# Camera.net
KiCad netlist of a schematic drawn in Altium Designer
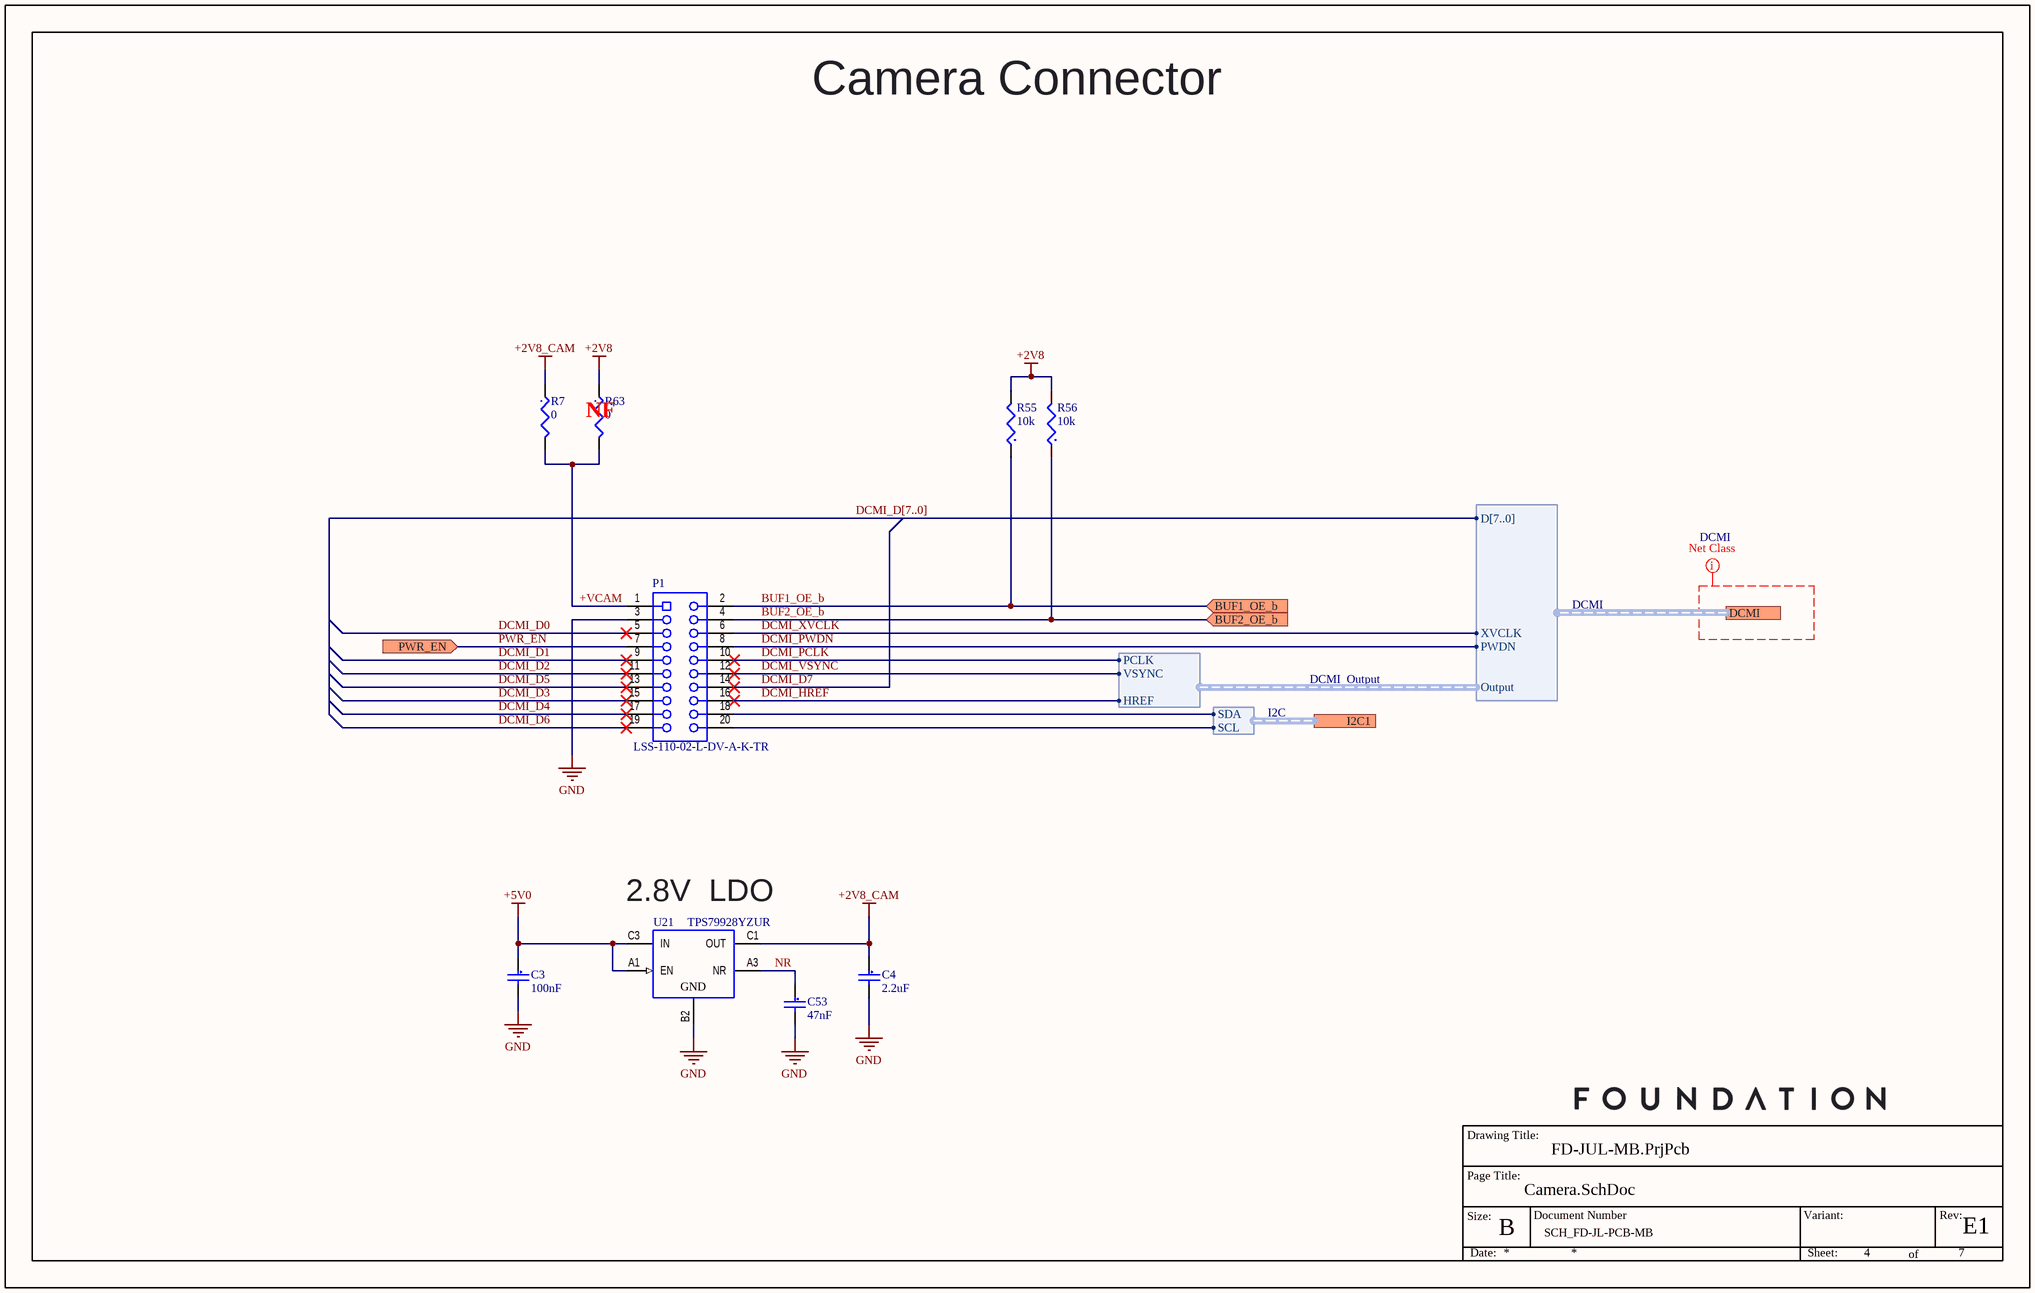
[diagram p0: Camera.SchDoc]

(export (version "E")
  (design (tool "Eeschema 10.0.6"))
  (components
    (comp (ref "C3")
      (value "CAP CER 0.1uF 16V 10% X7R 0402")
      (footprint "CAPC0402(1005)55_L")
      (description "0.1µF ±10% 16V Ceramic Capacitor X7R 0402 (1005 Metric)")
      (fields
        (field (name "CAPACITANCE") "100nF")
        (field (name "TOLERANCE") "10%")
        (field (name "VOLTAGE") "16V")
      )
      (libsource (lib "Altium Concord Pro on A365") (part "CAP-NP-2"))
    )
    (comp (ref "C4")
      (value "CAP CER 2.2uF 6.3V 10% X5R 0402")
      (footprint "CAPC0402(1005)55_L")
      (description "2.2µF ±10% 6.3V Ceramic Capacitor X5R 0402 (1005 Metric)")
      (fields (field (name "CAPACITANCE") "2.2uF") (field (name "TOLERANCE") "10%"))
      (libsource (lib "Altium Concord Pro on A365") (part "CAP-NP-2"))
    )
    (comp (ref "C53")
      (value "CAP CER 0.047uF 10V 10% X7R 0402")
      (footprint "CAPC0402(1005)55_L")
      (description "0.047µF ±10% 10V Ceramic Capacitor X7R 0402 (1005 Metric)")
      (fields (field (name "CAPACITANCE") "47nF"))
      (libsource (lib "Altium Concord Pro on A365") (part "CAP-NP-2"))
    )
    (comp (ref "P1")
      (value "LSS-110-02-L-DV-A-K-TR")
      (footprint "SMTC - LSS-110-02-L-DV-A_V")
      (description "20 Position Connector Self Mating, Non-Gendered Surface Mount Gold")
      (libsource (lib "Altium Concord Pro on A365") (part "CN-2P-F-R20"))
    )
    (comp (ref "R7")
      (value "RES 0 OHM JUMPER 1/16W 0402")
      (footprint "RESC0402(1005)_L")
      (description "0 Ohms Jumper 0.063W, 1/16W Chip Resistor 0402 (1005 Metric)")
      (fields (field (name "RESISTANCE") "0") (field (name "TOLERANCE") "5%"))
      (libsource (lib "Altium Concord Pro on A365") (part "RES-2"))
    )
    (comp (ref "R55")
      (value "RES 10K 1/16W 1% 0402")
      (footprint "RESC0402(1005)_L")
      (description "10 kOhms ±1% 0.063W, 1/16W Chip Resistor 0402 (1005 Metric)")
      (fields (field (name "RESISTANCE") "10k") (field (name "TOLERANCE") "1%"))
      (libsource (lib "Altium Concord Pro on A365") (part "RES-2"))
    )
    (comp (ref "R56")
      (value "RES 10K 1/16W 1% 0402")
      (footprint "RESC0402(1005)_L")
      (description "10 kOhms ±1% 0.063W, 1/16W Chip Resistor 0402 (1005 Metric)")
      (fields (field (name "RESISTANCE") "10k") (field (name "TOLERANCE") "1%"))
      (libsource (lib "Altium Concord Pro on A365") (part "RES-2"))
    )
    (comp (ref "R63")
      (value "RES 0 OHM JUMPER 1/16W 0402")
      (footprint "RESC0402(1005)_L")
      (description "0 Ohms Jumper 0.063W, 1/16W Chip Resistor 0402 (1005 Metric)")
      (fields (field (name "RESISTANCE") "0") (field (name "TOLERANCE") "5%"))
      (libsource (lib "Altium Concord Pro on A365") (part "RES-2"))
    )
    (comp (ref "U21")
      (value "TPS79928YZUR")
      (footprint "TI - DSBGA-YZU-5_V")
      (description "Linear Voltage Regulator IC  1 Output  200mA 5-DSBGA (1x1.37)")
      (libsource (lib "Altium Concord Pro on A365") (part "TPS79928YZU"))
    )
  )
  (nets
    (net (code "4") (name "+2V8") (class "Default")
      (node (ref "R55") (pin "2") (pinfunction "2_2") (pintype "passive"))
      (node (ref "R56") (pin "2") (pinfunction "2_2") (pintype "passive"))
      (node (ref "R63") (pin "1") (pinfunction "1_1") (pintype "passive"))
    )
    (net (code "5") (name "+2V8_CAM") (class "Default")
      (node (ref "C4") (pin "1") (pinfunction "1_1") (pintype "passive"))
      (node (ref "R7") (pin "1") (pinfunction "1_1") (pintype "passive"))
      (node (ref "U21") (pin "C1") (pinfunction "OUT_C1") (pintype "power_in"))
    )
    (net (code "6") (name "+5V0") (class "Default")
      (node (ref "C3") (pin "1") (pinfunction "1_1") (pintype "passive"))
      (node (ref "U21") (pin "A1") (pinfunction "EN_A1") (pintype "input"))
      (node (ref "U21") (pin "C3") (pinfunction "IN_C3") (pintype "power_in"))
    )
    (net (code "7") (name "/+VCAM") (class "Default")
      (node (ref "P1") (pin "1") (pinfunction "1_1") (pintype "passive"))
      (node (ref "R63") (pin "2") (pinfunction "2_2") (pintype "passive"))
      (node (ref "R7") (pin "2") (pinfunction "2_2") (pintype "passive"))
    )
    (net (code "8") (name "/BUF1_OE_b") (class "Default")
      (node (ref "P1") (pin "2") (pinfunction "2_2") (pintype "passive"))
      (node (ref "R55") (pin "1") (pinfunction "1_1") (pintype "passive"))
    )
    (net (code "9") (name "/BUF2_OE_b") (class "Default")
      (node (ref "P1") (pin "4") (pinfunction "4_4") (pintype "passive"))
      (node (ref "R56") (pin "1") (pinfunction "1_1") (pintype "passive"))
    )
    (net (code "10") (name "/DCMI_D0") (class "Default")
      (node (ref "P1") (pin "5") (pinfunction "5_5") (pintype "passive+no_connect"))
    )
    (net (code "11") (name "/DCMI_D1") (class "Default")
      (node (ref "P1") (pin "9") (pinfunction "9_9") (pintype "passive+no_connect"))
    )
    (net (code "12") (name "/DCMI_D2") (class "Default")
      (node (ref "P1") (pin "11") (pinfunction "11_11") (pintype "passive+no_connect"))
    )
    (net (code "13") (name "/DCMI_D3") (class "Default")
      (node (ref "P1") (pin "15") (pinfunction "15_15") (pintype "passive+no_connect"))
    )
    (net (code "14") (name "/DCMI_D4") (class "Default")
      (node (ref "P1") (pin "17") (pinfunction "17_17") (pintype "passive+no_connect"))
    )
    (net (code "15") (name "/DCMI_D5") (class "Default")
      (node (ref "P1") (pin "13") (pinfunction "13_13") (pintype "passive+no_connect"))
    )
    (net (code "16") (name "/DCMI_D6") (class "Default")
      (node (ref "P1") (pin "19") (pinfunction "19_19") (pintype "passive+no_connect"))
    )
    (net (code "17") (name "/DCMI_D7") (class "Default")
      (node (ref "P1") (pin "14") (pinfunction "14_14") (pintype "passive+no_connect"))
    )
    (net (code "19") (name "/DCMI_HREF") (class "Default")
      (node (ref "P1") (pin "16") (pinfunction "16_16") (pintype "passive+no_connect"))
    )
    (net (code "20") (name "/DCMI_PCLK") (class "Default")
      (node (ref "P1") (pin "10") (pinfunction "10_10") (pintype "passive+no_connect"))
    )
    (net (code "21") (name "/DCMI_PWDN") (class "Default")
      (node (ref "P1") (pin "8") (pinfunction "8_8") (pintype "passive"))
    )
    (net (code "22") (name "/DCMI_VSYNC") (class "Default")
      (node (ref "P1") (pin "12") (pinfunction "12_12") (pintype "passive+no_connect"))
    )
    (net (code "23") (name "/DCMI_XVCLK") (class "Default")
      (node (ref "P1") (pin "6") (pinfunction "6_6") (pintype "passive"))
    )
    (net (code "24") (name "/NR") (class "Default")
      (node (ref "C53") (pin "1") (pinfunction "1_1") (pintype "passive"))
      (node (ref "U21") (pin "A3") (pinfunction "NR_A3") (pintype "passive"))
    )
    (net (code "25") (name "/PWR_EN") (class "Default")
      (node (ref "P1") (pin "7") (pinfunction "7_7") (pintype "passive"))
    )
    (net (code "26") (name "/SCL") (class "Default")
      (node (ref "P1") (pin "20") (pinfunction "20_20") (pintype "passive"))
    )
    (net (code "27") (name "/SDA") (class "Default")
      (node (ref "P1") (pin "18") (pinfunction "18_18") (pintype "passive"))
    )
    (net (code "31") (name "GND") (class "Default")
      (node (ref "C3") (pin "2") (pinfunction "2_2") (pintype "passive"))
      (node (ref "C4") (pin "2") (pinfunction "2_2") (pintype "passive"))
      (node (ref "C53") (pin "2") (pinfunction "2_2") (pintype "passive"))
      (node (ref "P1") (pin "3") (pinfunction "3_3") (pintype "passive"))
      (node (ref "U21") (pin "B2") (pinfunction "GND_B2") (pintype "power_in"))
    )
  )
)
